# programming.net
KiCad netlist of a schematic drawn in EAGLE
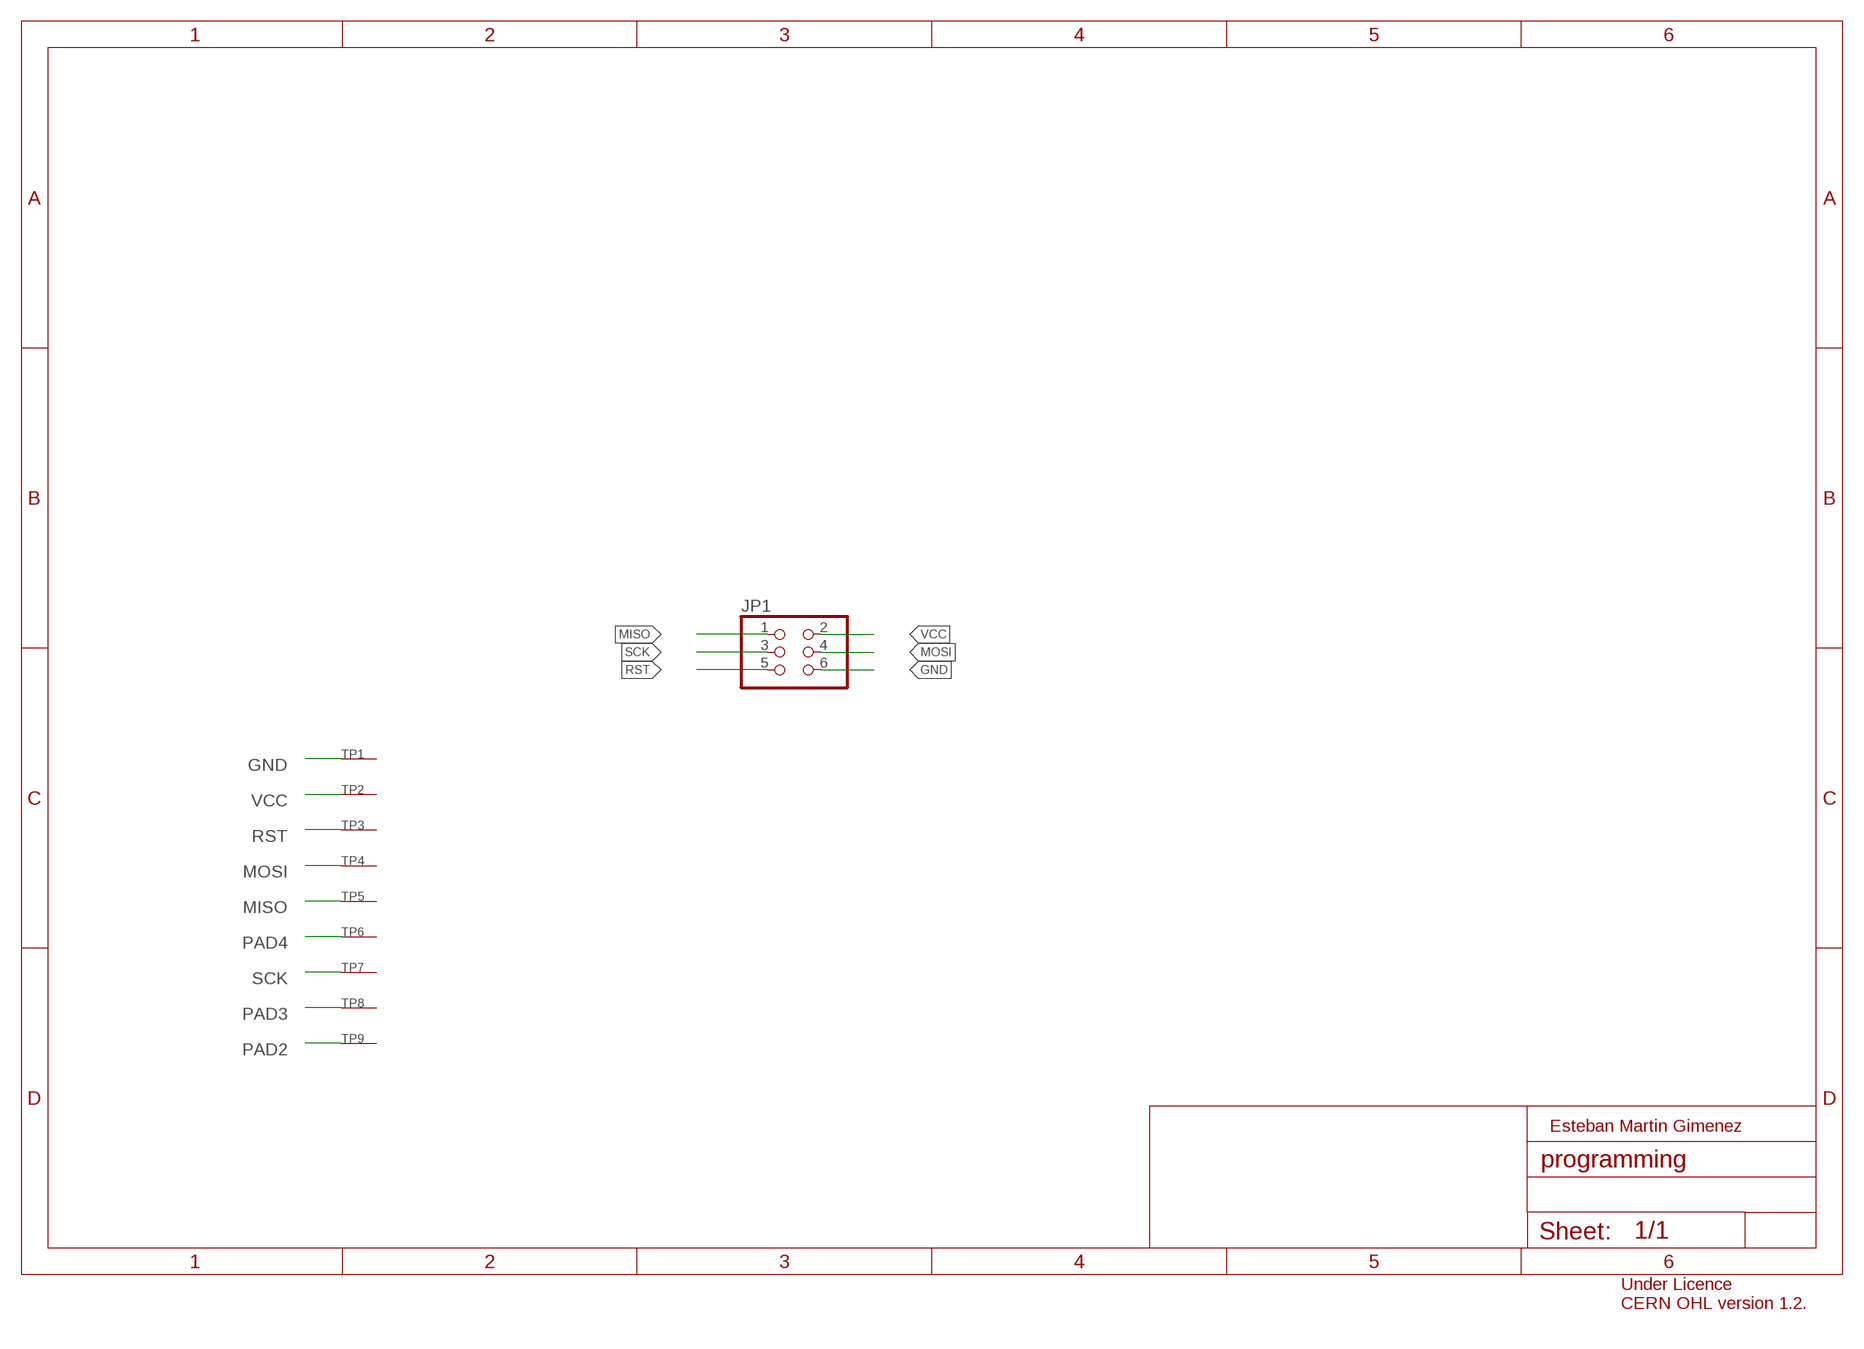
[diagram p0: schematic, sheet 1]

(export (version "E")
  (design (tool "Eeschema 10.0.6"))
  (components
    (comp (ref "JP1")
      (value "PINHD-2X3-SMD")
      (footprint "eagle-import:2X03SMD")
      (libsource (lib "eagle-import") (part "PINHD-2X3-SMD"))
    )
    (comp (ref "TP1")
      (value "SEWTAP-2.0IN")
      (footprint "eagle-import:SEWINGTAP_2.0")
      (libsource (lib "eagle-import") (part "SEWTAP-2.0IN"))
    )
    (comp (ref "TP2")
      (value "SEWTAP-2.0IN")
      (footprint "eagle-import:SEWINGTAP_2.0")
      (libsource (lib "eagle-import") (part "SEWTAP-2.0IN"))
    )
    (comp (ref "TP3")
      (value "SEWTAP-2.0IN")
      (footprint "eagle-import:SEWINGTAP_2.0")
      (libsource (lib "eagle-import") (part "SEWTAP-2.0IN"))
    )
    (comp (ref "TP4")
      (value "SEWTAP-2.0IN")
      (footprint "eagle-import:SEWINGTAP_2.0")
      (libsource (lib "eagle-import") (part "SEWTAP-2.0IN"))
    )
    (comp (ref "TP5")
      (value "SEWTAP-2.0IN")
      (footprint "eagle-import:SEWINGTAP_2.0")
      (libsource (lib "eagle-import") (part "SEWTAP-2.0IN"))
    )
    (comp (ref "TP6")
      (value "SEWTAP-2.0IN")
      (footprint "eagle-import:SEWINGTAP_2.0")
      (libsource (lib "eagle-import") (part "SEWTAP-2.0IN"))
    )
    (comp (ref "TP7")
      (value "SEWTAP-2.0IN")
      (footprint "eagle-import:SEWINGTAP_2.0")
      (libsource (lib "eagle-import") (part "SEWTAP-2.0IN"))
    )
    (comp (ref "TP8")
      (value "SEWTAP-2.0IN")
      (footprint "eagle-import:SEWINGTAP_2.0")
      (libsource (lib "eagle-import") (part "SEWTAP-2.0IN"))
    )
    (comp (ref "TP9")
      (value "SEWTAP-2.0IN")
      (footprint "eagle-import:SEWINGTAP_2.0")
      (libsource (lib "eagle-import") (part "SEWTAP-2.0IN"))
    )
  )
  (nets
    (net (code "1") (name "/PAD2") (class "Default")
      (node (ref "TP9") (pin "P$1") (pinfunction "SEW_P$1") (pintype "bidirectional"))
    )
    (net (code "2") (name "/PAD3") (class "Default")
      (node (ref "TP8") (pin "P$1") (pinfunction "SEW_P$1") (pintype "bidirectional"))
    )
    (net (code "3") (name "/PAD4") (class "Default")
      (node (ref "TP6") (pin "P$1") (pinfunction "SEW_P$1") (pintype "bidirectional"))
    )
    (net (code "4") (name "GND") (class "Default")
      (node (ref "JP1") (pin "6") (pinfunction "6_6") (pintype "passive"))
      (node (ref "TP1") (pin "P$1") (pinfunction "SEW_P$1") (pintype "bidirectional"))
    )
    (net (code "5") (name "MISO") (class "Default")
      (node (ref "JP1") (pin "1") (pinfunction "1_1") (pintype "passive"))
      (node (ref "TP5") (pin "P$1") (pinfunction "SEW_P$1") (pintype "bidirectional"))
    )
    (net (code "6") (name "MOSI") (class "Default")
      (node (ref "JP1") (pin "4") (pinfunction "4_4") (pintype "passive"))
      (node (ref "TP4") (pin "P$1") (pinfunction "SEW_P$1") (pintype "bidirectional"))
    )
    (net (code "7") (name "RST") (class "Default")
      (node (ref "JP1") (pin "5") (pinfunction "5_5") (pintype "passive"))
      (node (ref "TP3") (pin "P$1") (pinfunction "SEW_P$1") (pintype "bidirectional"))
    )
    (net (code "8") (name "SCK") (class "Default")
      (node (ref "JP1") (pin "3") (pinfunction "3_3") (pintype "passive"))
      (node (ref "TP7") (pin "P$1") (pinfunction "SEW_P$1") (pintype "bidirectional"))
    )
    (net (code "9") (name "VCC") (class "Default")
      (node (ref "JP1") (pin "2") (pinfunction "2_2") (pintype "passive"))
      (node (ref "TP2") (pin "P$1") (pinfunction "SEW_P$1") (pintype "bidirectional"))
    )
  )
)
